# smartwatch_class_2_justincase.net
KiCad netlist of a schematic drawn in EAGLE
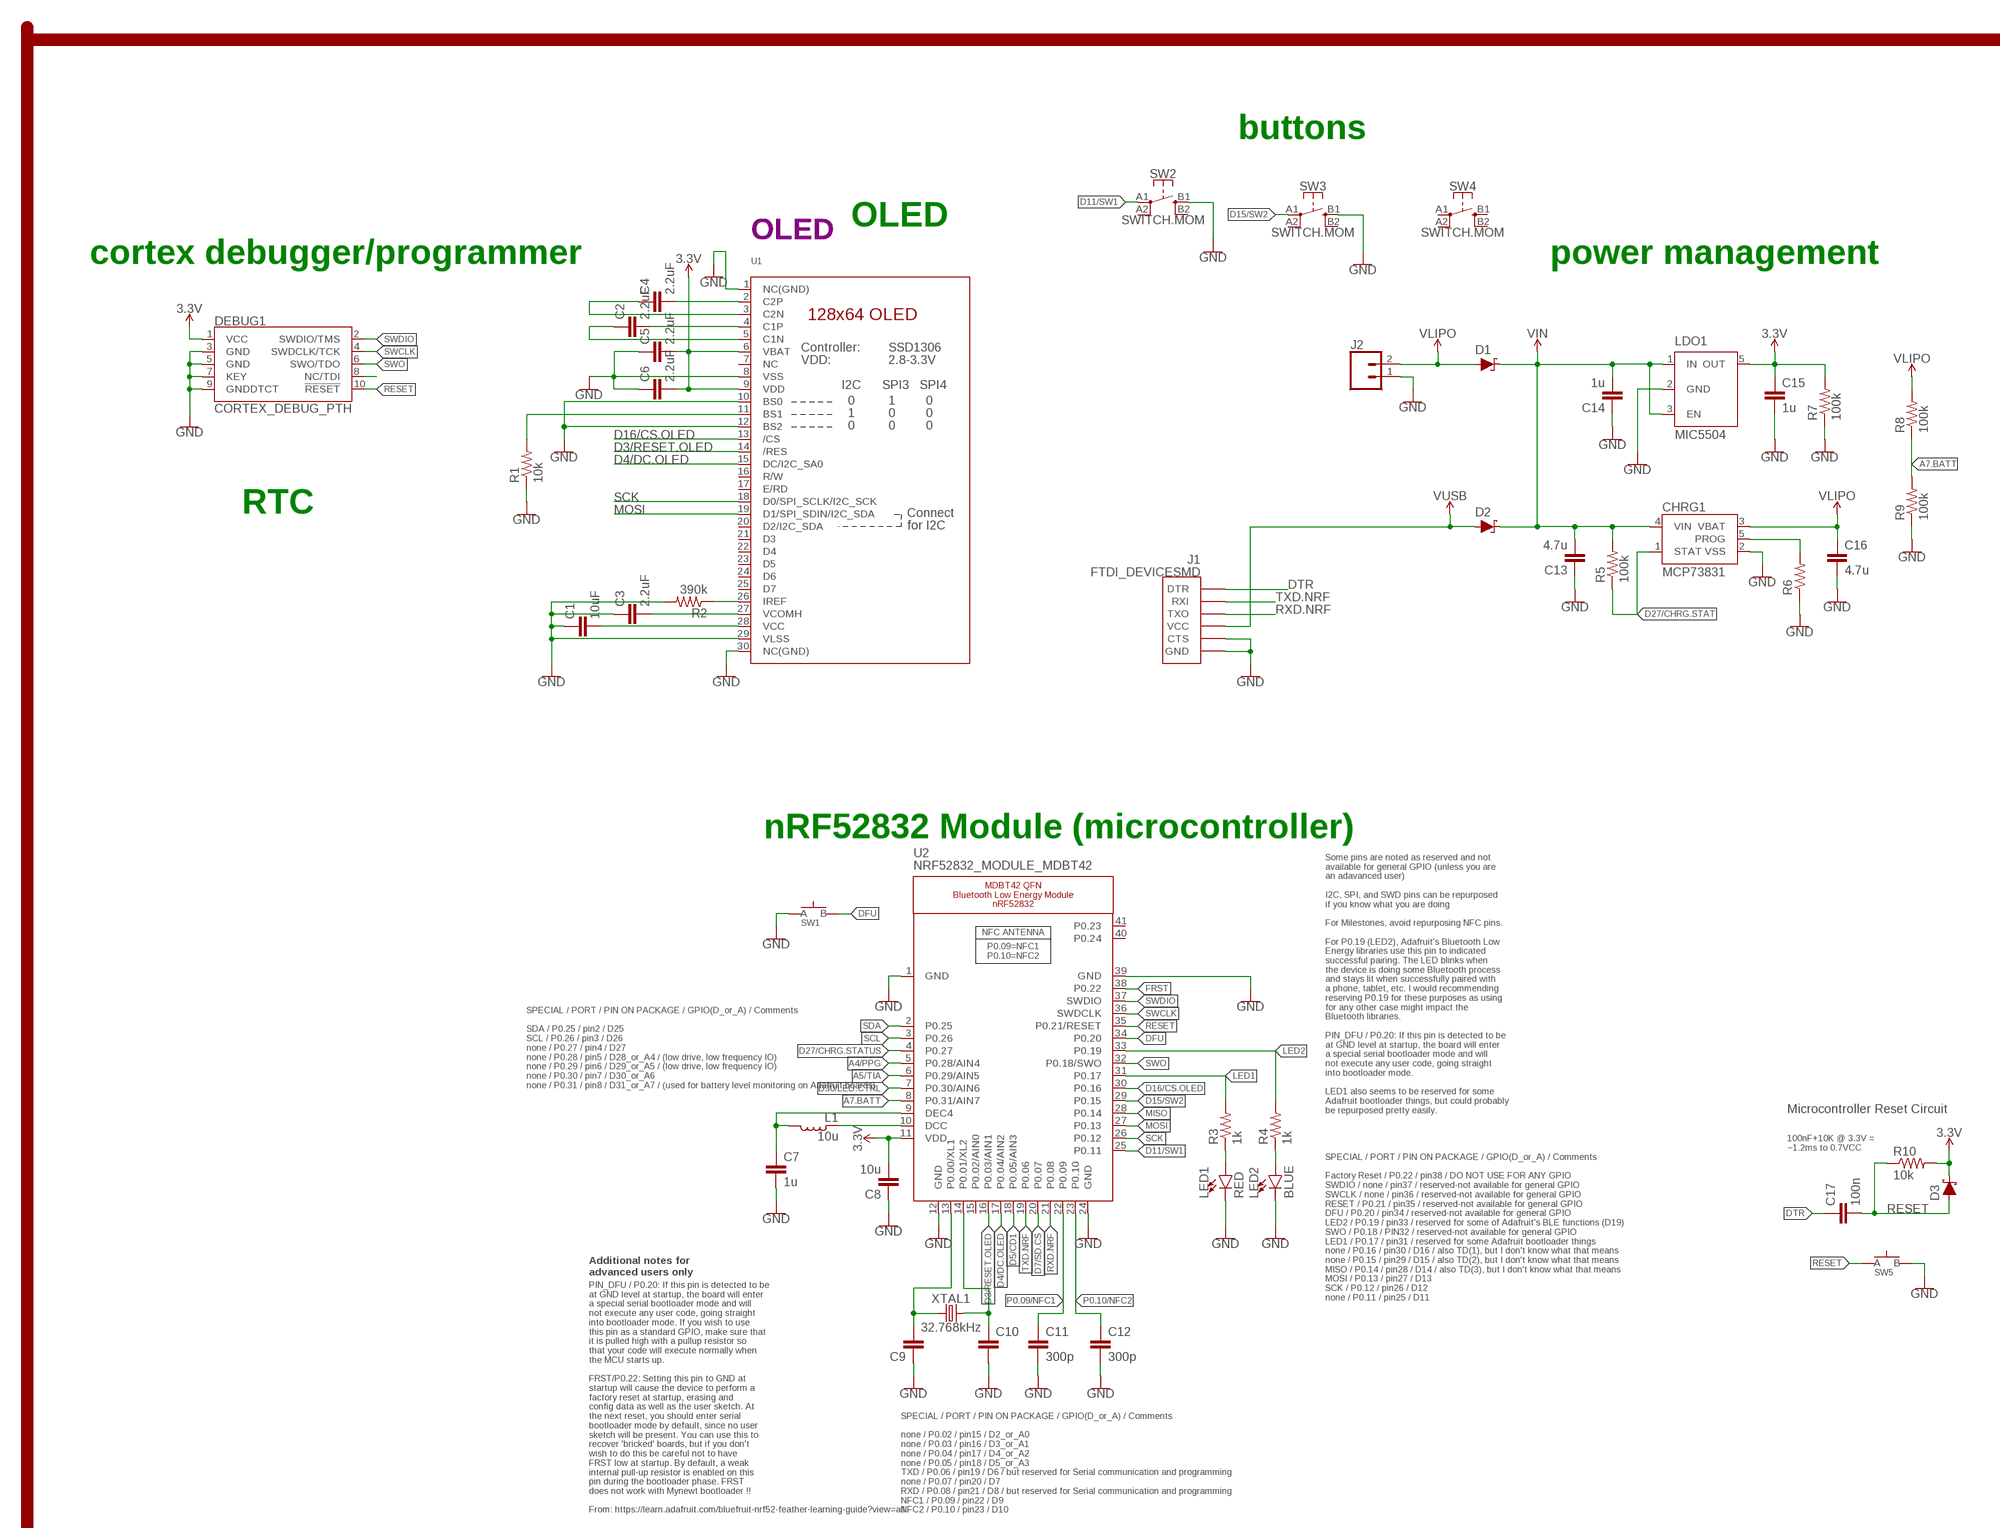
[diagram p0: schematic, sheet 1, part 1 of 2]
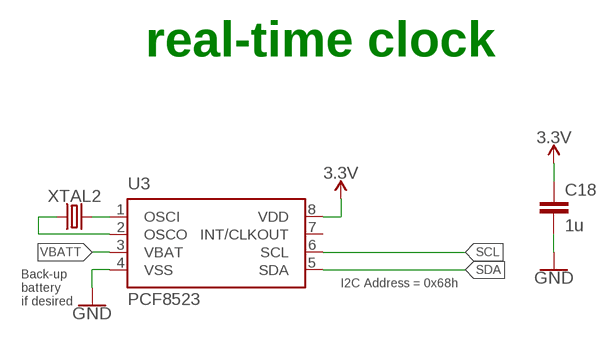
[diagram p1: schematic, sheet 1, part 2 of 2]

(export (version "E")
  (design (tool "Eeschema 10.0.6"))
  (components
    (comp (ref "C1")
      (value "10uF")
      (footprint "eagle-import:C0603")
      (libsource (lib "eagle-import") (part "CAPACITOR0603"))
    )
    (comp (ref "C2")
      (value "2.2uF")
      (footprint "eagle-import:C0603")
      (libsource (lib "eagle-import") (part "CAPACITOR0603"))
    )
    (comp (ref "C3")
      (value "2.2uF")
      (footprint "eagle-import:C0603")
      (libsource (lib "eagle-import") (part "CAPACITOR0603"))
    )
    (comp (ref "C4")
      (value "2.2uF")
      (footprint "eagle-import:C0603")
      (libsource (lib "eagle-import") (part "CAPACITOR0603"))
    )
    (comp (ref "C5")
      (value "2.2uF")
      (footprint "eagle-import:C0603")
      (libsource (lib "eagle-import") (part "CAPACITOR0603"))
    )
    (comp (ref "C6")
      (value "2.2uF")
      (footprint "eagle-import:C0603")
      (libsource (lib "eagle-import") (part "CAPACITOR0603"))
    )
    (comp (ref "C7")
      (value "1u")
      (footprint "eagle-import:C0603")
      (libsource (lib "eagle-import") (part "CAPACITOR0603"))
    )
    (comp (ref "C8")
      (value "10u")
      (footprint "eagle-import:C0805")
      (libsource (lib "eagle-import") (part "CAPACITOR0805"))
    )
    (comp (ref "C9")
      (value "CAPACITOR0603")
      (footprint "eagle-import:C0603")
      (libsource (lib "eagle-import") (part "CAPACITOR0603"))
    )
    (comp (ref "C10")
      (value "CAPACITOR0603")
      (footprint "eagle-import:C0603")
      (libsource (lib "eagle-import") (part "CAPACITOR0603"))
    )
    (comp (ref "C11")
      (value "300p")
      (footprint "eagle-import:C0603")
      (libsource (lib "eagle-import") (part "CAPACITOR0603"))
    )
    (comp (ref "C12")
      (value "300p")
      (footprint "eagle-import:C0603")
      (libsource (lib "eagle-import") (part "CAPACITOR0603"))
    )
    (comp (ref "C13")
      (value "4.7u")
      (footprint "eagle-import:C0603")
      (libsource (lib "eagle-import") (part "CAPACITOR0603"))
    )
    (comp (ref "C14")
      (value "1u")
      (footprint "eagle-import:C0603")
      (libsource (lib "eagle-import") (part "CAPACITOR0603"))
    )
    (comp (ref "C15")
      (value "1u")
      (footprint "eagle-import:C0603")
      (libsource (lib "eagle-import") (part "CAPACITOR0603"))
    )
    (comp (ref "C16")
      (value "4.7u")
      (footprint "eagle-import:C0603")
      (libsource (lib "eagle-import") (part "CAPACITOR0603"))
    )
    (comp (ref "C17")
      (value "100n")
      (footprint "eagle-import:C0603")
      (libsource (lib "eagle-import") (part "CAPACITOR0603"))
    )
    (comp (ref "C18")
      (value "1u")
      (footprint "eagle-import:C0603")
      (libsource (lib "eagle-import") (part "CAPACITOR0603"))
    )
    (comp (ref "CHRG1")
      (value "MCP73831")
      (footprint "eagle-import:SOT23-5")
      (libsource (lib "eagle-import") (part "MCP73831"))
    )
    (comp (ref "D1")
      (value "SCHOTTKY-USC")
      (footprint "eagle-import:USC")
      (libsource (lib "eagle-import") (part "SCHOTTKY-USC"))
    )
    (comp (ref "D2")
      (value "SCHOTTKY-USC")
      (footprint "eagle-import:USC")
      (libsource (lib "eagle-import") (part "SCHOTTKY-USC"))
    )
    (comp (ref "D3")
      (value "SCHOTTKY-USC")
      (footprint "eagle-import:USC")
      (libsource (lib "eagle-import") (part "SCHOTTKY-USC"))
    )
    (comp (ref "DEBUG1")
      (value "CORTEX_DEBUG_PTH")
      (footprint "eagle-import:2X5-PTH-1.27MM")
      (libsource (lib "eagle-import") (part "CORTEX_DEBUG_PTH"))
    )
    (comp (ref "J1")
      (value "FTDI_DEVICESMD")
      (footprint "eagle-import:FTDI-SMD")
      (libsource (lib "eagle-import") (part "FTDI_DEVICESMD"))
    )
    (comp (ref "J2")
      (value "CONN_02")
      (footprint "eagle-import:1X02")
      (libsource (lib "eagle-import") (part "CONN_02"))
    )
    (comp (ref "L1")
      (value "10u")
      (footprint "eagle-import:L0603")
      (libsource (lib "eagle-import") (part "INDUCTOR0603"))
    )
    (comp (ref "LDO1")
      (value "MIC5504")
      (footprint "eagle-import:SOT23-5")
      (libsource (lib "eagle-import") (part "MIC5504"))
    )
    (comp (ref "LED1")
      (value "RED")
      (footprint "eagle-import:LED-0603")
      (libsource (lib "eagle-import") (part "LED0603"))
    )
    (comp (ref "LED2")
      (value "BLUE")
      (footprint "eagle-import:LED-0603")
      (libsource (lib "eagle-import") (part "LED0603"))
    )
    (comp (ref "R1")
      (value "10k")
      (footprint "eagle-import:R0603")
      (libsource (lib "eagle-import") (part "RESISTOR0603"))
    )
    (comp (ref "R2")
      (value "390k")
      (footprint "eagle-import:R0603")
      (libsource (lib "eagle-import") (part "RESISTOR0603"))
    )
    (comp (ref "R3")
      (value "1k")
      (footprint "eagle-import:R0603")
      (libsource (lib "eagle-import") (part "RESISTOR0603"))
    )
    (comp (ref "R4")
      (value "1k")
      (footprint "eagle-import:R0603")
      (libsource (lib "eagle-import") (part "RESISTOR0603"))
    )
    (comp (ref "R5")
      (value "100k")
      (footprint "eagle-import:R0603")
      (libsource (lib "eagle-import") (part "RESISTOR0603"))
    )
    (comp (ref "R6")
      (value "RESISTOR0603")
      (footprint "eagle-import:R0603")
      (libsource (lib "eagle-import") (part "RESISTOR0603"))
    )
    (comp (ref "R7")
      (value "100k")
      (footprint "eagle-import:R0603")
      (libsource (lib "eagle-import") (part "RESISTOR0603"))
    )
    (comp (ref "R8")
      (value "100k")
      (footprint "eagle-import:R0603")
      (libsource (lib "eagle-import") (part "RESISTOR0603"))
    )
    (comp (ref "R9")
      (value "100k")
      (footprint "eagle-import:R0603")
      (libsource (lib "eagle-import") (part "RESISTOR0603"))
    )
    (comp (ref "R10")
      (value "10k")
      (footprint "eagle-import:R0603")
      (libsource (lib "eagle-import") (part "RESISTOR0603"))
    )
    (comp (ref "SW1")
      (value "SPST-PTS830GG140-COPY.1-3")
      (footprint "eagle-import:BUTTON-GULLWING")
      (libsource (lib "eagle-import") (part "SPST-PTS830GG140-COPY.1-3"))
    )
    (comp (ref "SW2")
      (value "SWITCH.MOM")
      (footprint "eagle-import:TACTILE_SWITCH_SMD_6.2MM_TALL")
      (libsource (lib "eagle-import") (part "SWITCH.MOM"))
    )
    (comp (ref "SW3")
      (value "SWITCH.MOM")
      (footprint "eagle-import:TACTILE_SWITCH_SMD_6.2MM_TALL")
      (libsource (lib "eagle-import") (part "SWITCH.MOM"))
    )
    (comp (ref "SW4")
      (value "SWITCH.MOM")
      (footprint "eagle-import:TACTILE_SWITCH_SMD_6.2MM_TALL")
      (libsource (lib "eagle-import") (part "SWITCH.MOM"))
    )
    (comp (ref "SW5")
      (value "SPST-PTS830GG140-COPY.1-3")
      (footprint "eagle-import:BUTTON-GULLWING")
      (libsource (lib "eagle-import") (part "SPST-PTS830GG140-COPY.1-3"))
    )
    (comp (ref "U1")
      (value "DISP_OLED_UG-2864HSWEG01-NO-WRAPAROUND")
      (footprint "eagle-import:UG-2864HSWEG01_0.96IN_NO-WRAPAROUND")
      (libsource (lib "eagle-import") (part "DISP_OLED_UG-2864HSWEG01-NO-WRAPAROUND"))
    )
    (comp (ref "U2")
      (value "NRF52832_MODULE_MDBT42")
      (footprint "eagle-import:BLE_MODULE_RAYTAC_MDBT42")
      (libsource (lib "eagle-import") (part "NRF52832_MODULE_MDBT42"))
    )
    (comp (ref "U3")
      (value "PCF8523")
      (footprint "eagle-import:SO8")
      (libsource (lib "eagle-import") (part "PCF8523"))
    )
    (comp (ref "XTAL1")
      (value "32.768kHz")
      (footprint "eagle-import:2-SMD.NOLEAD.2.0MMTO1.2MM")
      (libsource (lib "eagle-import") (part "CRYSTALECS-.327-12.5-12-C-TR"))
    )
    (comp (ref "XTAL2")
      (value "32.7680kHz")
      (footprint "eagle-import:2-SMD.NOLEAD.2.0MMTO1.2MM")
      (fields (field (name "FREQ") "32.7680KHZ"))
      (libsource (lib "eagle-import") (part "CRYSTALECS-.327-12.5-12-C-TR"))
    )
  )
  (nets
    (net (code "1") (name "3.3V") (class "Default")
      (node (ref "C15") (pin "1") (pinfunction "1_1") (pintype "passive"))
      (node (ref "C18") (pin "1") (pinfunction "1_1") (pintype "passive"))
      (node (ref "C5") (pin "2") (pinfunction "2_2") (pintype "passive"))
      (node (ref "C6") (pin "2") (pinfunction "2_2") (pintype "passive"))
      (node (ref "C8") (pin "2") (pinfunction "2_2") (pintype "passive"))
      (node (ref "D3") (pin "-") (pinfunction "C_-") (pintype "passive"))
      (node (ref "DEBUG1") (pin "1") (pinfunction "VCC_1") (pintype "bidirectional"))
      (node (ref "LDO1") (pin "5") (pinfunction "OUT_5") (pintype "bidirectional"))
      (node (ref "R10") (pin "2") (pinfunction "2_2") (pintype "passive"))
      (node (ref "R7") (pin "2") (pinfunction "2_2") (pintype "passive"))
      (node (ref "U1") (pin "6") (pinfunction "VBAT_6") (pintype "input"))
      (node (ref "U1") (pin "9") (pinfunction "VDD_9") (pintype "power_in"))
      (node (ref "U2") (pin "11") (pinfunction "VDD_11") (pintype "bidirectional"))
      (node (ref "U3") (pin "8") (pinfunction "VDD_8") (pintype "power_in"))
    )
    (net (code "2") (name "A4{slash}PPG") (class "Default")
      (node (ref "U2") (pin "5") (pinfunction "P0.28/AIN4_5") (pintype "bidirectional"))
    )
    (net (code "3") (name "A5{slash}TIA") (class "Default")
      (node (ref "U2") (pin "6") (pinfunction "P0.29/AIN5_6") (pintype "bidirectional"))
    )
    (net (code "4") (name "A7.BATT") (class "Default")
      (node (ref "R8") (pin "1") (pinfunction "1_1") (pintype "passive"))
      (node (ref "R9") (pin "2") (pinfunction "2_2") (pintype "passive"))
      (node (ref "U2") (pin "8") (pinfunction "P0.31/AIN7_8") (pintype "bidirectional"))
    )
    (net (code "5") (name "D3{slash}RESET.OLED") (class "Default")
      (node (ref "U1") (pin "14") (pinfunction "/RES_14") (pintype "input"))
      (node (ref "U2") (pin "16") (pinfunction "P0.03/AIN1_16") (pintype "bidirectional"))
    )
    (net (code "6") (name "D4{slash}DC.OLED") (class "Default")
      (node (ref "U1") (pin "15") (pinfunction "DC/I2C_SA0_15") (pintype "input"))
      (node (ref "U2") (pin "17") (pinfunction "P0.04/AIN2_17") (pintype "bidirectional"))
    )
    (net (code "7") (name "D5{slash}CD1") (class "Default")
      (node (ref "U2") (pin "18") (pinfunction "P0.05/AIN3_18") (pintype "bidirectional"))
    )
    (net (code "8") (name "D7{slash}SD.CS") (class "Default")
      (node (ref "U2") (pin "20") (pinfunction "P0.07_20") (pintype "bidirectional"))
    )
    (net (code "9") (name "D11{slash}SW1") (class "Default")
      (node (ref "SW2") (pin "A1") (pinfunction "1_A1") (pintype "passive"))
      (node (ref "U2") (pin "25") (pinfunction "P0.11_25") (pintype "bidirectional"))
    )
    (net (code "10") (name "D15{slash}SW2") (class "Default")
      (node (ref "SW3") (pin "A1") (pinfunction "1_A1") (pintype "passive"))
      (node (ref "U2") (pin "29") (pinfunction "P0.15_29") (pintype "bidirectional"))
    )
    (net (code "11") (name "D16{slash}CS.OLED") (class "Default")
      (node (ref "U1") (pin "13") (pinfunction "/CS_13") (pintype "input"))
      (node (ref "U2") (pin "30") (pinfunction "P0.16_30") (pintype "bidirectional"))
    )
    (net (code "12") (name "D27{slash}CHRG.STAT") (class "Default")
      (node (ref "CHRG1") (pin "1") (pinfunction "STAT_1") (pintype "output"))
      (node (ref "R5") (pin "1") (pinfunction "1_1") (pintype "passive"))
    )
    (net (code "13") (name "D27{slash}CHRG.STATUS") (class "Default")
      (node (ref "U2") (pin "4") (pinfunction "P0.27_4") (pintype "bidirectional"))
    )
    (net (code "14") (name "D30{slash}LED.CTRL") (class "Default")
      (node (ref "U2") (pin "7") (pinfunction "P0.30/AIN6_7") (pintype "bidirectional"))
    )
    (net (code "15") (name "DFU") (class "Default")
      (node (ref "SW1") (pin "3") (pinfunction "B_3") (pintype "bidirectional"))
      (node (ref "U2") (pin "34") (pinfunction "P0.20_34") (pintype "bidirectional"))
    )
    (net (code "16") (name "DTR") (class "Default")
      (node (ref "C17") (pin "1") (pinfunction "1_1") (pintype "passive"))
      (node (ref "J1") (pin "DTR") (pinfunction "DTR_DTR") (pintype "bidirectional"))
    )
    (net (code "17") (name "FRST") (class "Default")
      (node (ref "U2") (pin "38") (pinfunction "P0.22_38") (pintype "bidirectional"))
    )
    (net (code "18") (name "GND") (class "Default")
      (node (ref "C1") (pin "1") (pinfunction "1_1") (pintype "passive"))
      (node (ref "C10") (pin "2") (pinfunction "2_2") (pintype "passive"))
      (node (ref "C11") (pin "2") (pinfunction "2_2") (pintype "passive"))
      (node (ref "C12") (pin "2") (pinfunction "2_2") (pintype "passive"))
      (node (ref "C13") (pin "1") (pinfunction "1_1") (pintype "passive"))
      (node (ref "C14") (pin "1") (pinfunction "1_1") (pintype "passive"))
      (node (ref "C15") (pin "2") (pinfunction "2_2") (pintype "passive"))
      (node (ref "C16") (pin "2") (pinfunction "2_2") (pintype "passive"))
      (node (ref "C18") (pin "2") (pinfunction "2_2") (pintype "passive"))
      (node (ref "C3") (pin "1") (pinfunction "1_1") (pintype "passive"))
      (node (ref "C5") (pin "1") (pinfunction "1_1") (pintype "passive"))
      (node (ref "C6") (pin "1") (pinfunction "1_1") (pintype "passive"))
      (node (ref "C7") (pin "2") (pinfunction "2_2") (pintype "passive"))
      (node (ref "C8") (pin "1") (pinfunction "1_1") (pintype "passive"))
      (node (ref "C9") (pin "1") (pinfunction "1_1") (pintype "passive"))
      (node (ref "CHRG1") (pin "2") (pinfunction "VSS_2") (pintype "power_in"))
      (node (ref "DEBUG1") (pin "3") (pinfunction "GND_3") (pintype "bidirectional"))
      (node (ref "DEBUG1") (pin "5") (pinfunction "GND_5") (pintype "bidirectional"))
      (node (ref "DEBUG1") (pin "7") (pinfunction "KEY_7") (pintype "bidirectional"))
      (node (ref "DEBUG1") (pin "9") (pinfunction "GNDDTCT_9") (pintype "bidirectional"))
      (node (ref "J1") (pin "CTS") (pinfunction "CTS_CTS") (pintype "bidirectional"))
      (node (ref "J1") (pin "GND") (pinfunction "GND_GND") (pintype "bidirectional"))
      (node (ref "J2") (pin "1") (pinfunction "1_1") (pintype "passive"))
      (node (ref "LDO1") (pin "2") (pinfunction "GND_2") (pintype "bidirectional"))
      (node (ref "LED1") (pin "C") (pinfunction "C_C") (pintype "passive"))
      (node (ref "LED2") (pin "C") (pinfunction "C_C") (pintype "passive"))
      (node (ref "R1") (pin "1") (pinfunction "1_1") (pintype "passive"))
      (node (ref "R2") (pin "2") (pinfunction "2_2") (pintype "passive"))
      (node (ref "R6") (pin "1") (pinfunction "1_1") (pintype "passive"))
      (node (ref "R7") (pin "1") (pinfunction "1_1") (pintype "passive"))
      (node (ref "R9") (pin "1") (pinfunction "1_1") (pintype "passive"))
      (node (ref "SW1") (pin "1") (pinfunction "A_1") (pintype "bidirectional"))
      (node (ref "SW2") (pin "B1") (pinfunction "3_B1") (pintype "passive"))
      (node (ref "SW3") (pin "B1") (pinfunction "3_B1") (pintype "passive"))
      (node (ref "SW5") (pin "3") (pinfunction "B_3") (pintype "bidirectional"))
      (node (ref "U1") (pin "1") (pinfunction "NC(GND)_1") (pintype "input"))
      (node (ref "U1") (pin "10") (pinfunction "BS0_10") (pintype "input"))
      (node (ref "U1") (pin "12") (pinfunction "BS2_12") (pintype "input"))
      (node (ref "U1") (pin "29") (pinfunction "VLSS_29") (pintype "power_in"))
      (node (ref "U1") (pin "30") (pinfunction "NC(GND)_30") (pintype "input"))
      (node (ref "U1") (pin "8") (pinfunction "VSS_8") (pintype "power_in"))
      (node (ref "U2") (pin "1") (pinfunction "GND_1") (pintype "bidirectional"))
      (node (ref "U2") (pin "12") (pinfunction "GND_12") (pintype "bidirectional"))
      (node (ref "U2") (pin "24") (pinfunction "GND_24") (pintype "bidirectional"))
      (node (ref "U2") (pin "39") (pinfunction "GND_39") (pintype "bidirectional"))
      (node (ref "U3") (pin "4") (pinfunction "VSS_4") (pintype "power_in"))
    )
    (net (code "19") (name "LED1") (class "Default")
      (node (ref "R3") (pin "2") (pinfunction "2_2") (pintype "passive"))
      (node (ref "U2") (pin "31") (pinfunction "P0.17_31") (pintype "bidirectional"))
    )
    (net (code "20") (name "LED2") (class "Default")
      (node (ref "R4") (pin "2") (pinfunction "2_2") (pintype "passive"))
      (node (ref "U2") (pin "33") (pinfunction "P0.19_33") (pintype "bidirectional"))
    )
    (net (code "21") (name "MISO") (class "Default")
      (node (ref "U2") (pin "28") (pinfunction "P0.14_28") (pintype "bidirectional"))
    )
    (net (code "22") (name "MOSI") (class "Default")
      (node (ref "U1") (pin "19") (pinfunction "D1/SPI_SDIN/I2C_SDA_19") (pintype "bidirectional"))
      (node (ref "U2") (pin "27") (pinfunction "P0.13_27") (pintype "bidirectional"))
    )
    (net (code "23") (name "Net-(CHRG1-PROG)") (class "Default")
      (node (ref "CHRG1") (pin "5") (pinfunction "PROG_5") (pintype "input"))
      (node (ref "R6") (pin "2") (pinfunction "2_2") (pintype "passive"))
    )
    (net (code "24") (name "Net-(LED1-PadA)") (class "Default")
      (node (ref "LED1") (pin "A") (pinfunction "A_A") (pintype "passive"))
      (node (ref "R3") (pin "1") (pinfunction "1_1") (pintype "passive"))
    )
    (net (code "25") (name "Net-(LED2-PadA)") (class "Default")
      (node (ref "LED2") (pin "A") (pinfunction "A_A") (pintype "passive"))
      (node (ref "R4") (pin "1") (pinfunction "1_1") (pintype "passive"))
    )
    (net (code "26") (name "Net-(U1-BS1)") (class "Default")
      (node (ref "R1") (pin "2") (pinfunction "2_2") (pintype "passive"))
      (node (ref "U1") (pin "11") (pinfunction "BS1_11") (pintype "input"))
    )
    (net (code "27") (name "Net-(U1-C1N)") (class "Default")
      (node (ref "C2") (pin "1") (pinfunction "1_1") (pintype "passive"))
      (node (ref "U1") (pin "5") (pinfunction "C1N_5") (pintype "input"))
    )
    (net (code "28") (name "Net-(U1-C1P)") (class "Default")
      (node (ref "C2") (pin "2") (pinfunction "2_2") (pintype "passive"))
      (node (ref "U1") (pin "4") (pinfunction "C1P_4") (pintype "input"))
    )
    (net (code "29") (name "Net-(U1-C2N)") (class "Default")
      (node (ref "C4") (pin "1") (pinfunction "1_1") (pintype "passive"))
      (node (ref "U1") (pin "3") (pinfunction "C2N_3") (pintype "input"))
    )
    (net (code "30") (name "Net-(U1-C2P)") (class "Default")
      (node (ref "C4") (pin "2") (pinfunction "2_2") (pintype "passive"))
      (node (ref "U1") (pin "2") (pinfunction "C2P_2") (pintype "input"))
    )
    (net (code "31") (name "Net-(U1-IREF)") (class "Default")
      (node (ref "R2") (pin "1") (pinfunction "1_1") (pintype "passive"))
      (node (ref "U1") (pin "26") (pinfunction "IREF_26") (pintype "input"))
    )
    (net (code "32") (name "Net-(U1-VCC)") (class "Default")
      (node (ref "C1") (pin "2") (pinfunction "2_2") (pintype "passive"))
      (node (ref "U1") (pin "28") (pinfunction "VCC_28") (pintype "power_in"))
    )
    (net (code "33") (name "Net-(U1-VCOMH)") (class "Default")
      (node (ref "C3") (pin "2") (pinfunction "2_2") (pintype "passive"))
      (node (ref "U1") (pin "27") (pinfunction "VCOMH_27") (pintype "output"))
    )
    (net (code "34") (name "Net-(U2-DCC)") (class "Default")
      (node (ref "L1") (pin "1") (pinfunction "1_1") (pintype "passive"))
      (node (ref "U2") (pin "10") (pinfunction "DCC_10") (pintype "bidirectional"))
    )
    (net (code "35") (name "Net-(U2-DEC4)") (class "Default")
      (node (ref "C7") (pin "1") (pinfunction "1_1") (pintype "passive"))
      (node (ref "L1") (pin "2") (pinfunction "2_2") (pintype "passive"))
      (node (ref "U2") (pin "9") (pinfunction "DEC4_9") (pintype "bidirectional"))
    )
    (net (code "36") (name "Net-(U2-P0.00{slash}XL1)") (class "Default")
      (node (ref "C9") (pin "2") (pinfunction "2_2") (pintype "passive"))
      (node (ref "U2") (pin "13") (pinfunction "P0.00/XL1_13") (pintype "bidirectional"))
      (node (ref "XTAL1") (pin "P$1") (pinfunction "1_P$1") (pintype "passive"))
    )
    (net (code "37") (name "Net-(U2-P0.01{slash}XL2)") (class "Default")
      (node (ref "C10") (pin "1") (pinfunction "1_1") (pintype "passive"))
      (node (ref "U2") (pin "14") (pinfunction "P0.01/XL2_14") (pintype "bidirectional"))
      (node (ref "XTAL1") (pin "P$2") (pinfunction "2_P$2") (pintype "passive"))
    )
    (net (code "38") (name "Net-(U3-OSCI)") (class "Default")
      (node (ref "U3") (pin "1") (pinfunction "OSCI_1") (pintype "bidirectional"))
      (node (ref "XTAL2") (pin "P$2") (pinfunction "2_P$2") (pintype "passive"))
    )
    (net (code "39") (name "Net-(U3-OSCO)") (class "Default")
      (node (ref "U3") (pin "2") (pinfunction "OSCO_2") (pintype "bidirectional"))
      (node (ref "XTAL2") (pin "P$1") (pinfunction "1_P$1") (pintype "passive"))
    )
    (net (code "40") (name "P0.09{slash}NFC1") (class "Default")
      (node (ref "C11") (pin "1") (pinfunction "1_1") (pintype "passive"))
      (node (ref "U2") (pin "22") (pinfunction "P0.09_22") (pintype "bidirectional"))
    )
    (net (code "41") (name "P0.10{slash}NFC2") (class "Default")
      (node (ref "C12") (pin "1") (pinfunction "1_1") (pintype "passive"))
      (node (ref "U2") (pin "23") (pinfunction "P0.10_23") (pintype "bidirectional"))
    )
    (net (code "42") (name "RESET") (class "Default")
      (node (ref "C17") (pin "2") (pinfunction "2_2") (pintype "passive"))
      (node (ref "D3") (pin "+") (pinfunction "A_+") (pintype "passive"))
      (node (ref "DEBUG1") (pin "10") (pinfunction "~{RESET}_10") (pintype "bidirectional"))
      (node (ref "R10") (pin "1") (pinfunction "1_1") (pintype "passive"))
      (node (ref "SW5") (pin "1") (pinfunction "A_1") (pintype "bidirectional"))
      (node (ref "U2") (pin "35") (pinfunction "P0.21/RESET_35") (pintype "bidirectional"))
    )
    (net (code "43") (name "RXD.NRF") (class "Default")
      (node (ref "J1") (pin "TXO") (pinfunction "TXO_TXO") (pintype "bidirectional"))
      (node (ref "U2") (pin "21") (pinfunction "P0.08_21") (pintype "bidirectional"))
    )
    (net (code "44") (name "SCK") (class "Default")
      (node (ref "U1") (pin "18") (pinfunction "D0/SPI_SCLK/I2C_SCK_18") (pintype "bidirectional"))
      (node (ref "U2") (pin "26") (pinfunction "P0.12_26") (pintype "bidirectional"))
    )
    (net (code "45") (name "SCL") (class "Default")
      (node (ref "U2") (pin "3") (pinfunction "P0.26_3") (pintype "bidirectional"))
      (node (ref "U3") (pin "6") (pinfunction "SCL_6") (pintype "bidirectional"))
    )
    (net (code "46") (name "SDA") (class "Default")
      (node (ref "U2") (pin "2") (pinfunction "P0.25_2") (pintype "bidirectional"))
      (node (ref "U3") (pin "5") (pinfunction "SDA_5") (pintype "bidirectional"))
    )
    (net (code "47") (name "SWCLK") (class "Default")
      (node (ref "DEBUG1") (pin "4") (pinfunction "SWDCLK/TCK_4") (pintype "bidirectional"))
      (node (ref "U2") (pin "36") (pinfunction "SWDCLK_36") (pintype "bidirectional"))
    )
    (net (code "48") (name "SWDIO") (class "Default")
      (node (ref "DEBUG1") (pin "2") (pinfunction "SWDIO/TMS_2") (pintype "bidirectional"))
      (node (ref "U2") (pin "37") (pinfunction "SWDIO_37") (pintype "bidirectional"))
    )
    (net (code "49") (name "SWO") (class "Default")
      (node (ref "DEBUG1") (pin "6") (pinfunction "SWO/TDO_6") (pintype "bidirectional"))
      (node (ref "U2") (pin "32") (pinfunction "P0.18/SWO_32") (pintype "bidirectional"))
    )
    (net (code "50") (name "TXD.NRF") (class "Default")
      (node (ref "J1") (pin "RXI") (pinfunction "RXI_RXI") (pintype "bidirectional"))
      (node (ref "U2") (pin "19") (pinfunction "P0.06_19") (pintype "bidirectional"))
    )
    (net (code "51") (name "VBATT") (class "Default")
      (node (ref "U3") (pin "3") (pinfunction "VBAT_3") (pintype "power_in"))
    )
    (net (code "52") (name "VIN") (class "Default")
      (node (ref "C13") (pin "2") (pinfunction "2_2") (pintype "passive"))
      (node (ref "C14") (pin "2") (pinfunction "2_2") (pintype "passive"))
      (node (ref "CHRG1") (pin "4") (pinfunction "VIN_4") (pintype "power_in"))
      (node (ref "D1") (pin "-") (pinfunction "C_-") (pintype "passive"))
      (node (ref "D2") (pin "-") (pinfunction "C_-") (pintype "passive"))
      (node (ref "LDO1") (pin "1") (pinfunction "IN_1") (pintype "bidirectional"))
      (node (ref "LDO1") (pin "3") (pinfunction "EN_3") (pintype "bidirectional"))
      (node (ref "R5") (pin "2") (pinfunction "2_2") (pintype "passive"))
    )
    (net (code "53") (name "VLIPO") (class "Default")
      (node (ref "C16") (pin "1") (pinfunction "1_1") (pintype "passive"))
      (node (ref "CHRG1") (pin "3") (pinfunction "VBAT_3") (pintype "power_in"))
      (node (ref "D1") (pin "+") (pinfunction "A_+") (pintype "passive"))
      (node (ref "J2") (pin "2") (pinfunction "2_2") (pintype "passive"))
      (node (ref "R8") (pin "2") (pinfunction "2_2") (pintype "passive"))
    )
    (net (code "54") (name "VUSB") (class "Default")
      (node (ref "D2") (pin "+") (pinfunction "A_+") (pintype "passive"))
      (node (ref "J1") (pin "VCC") (pinfunction "VCC_VCC") (pintype "bidirectional"))
    )
    (net (code "55") (name "unconnected-(DEBUG1-NC{slash}TDI-Pad8)") (class "Default")
      (node (ref "DEBUG1") (pin "8") (pinfunction "NC/TDI_8") (pintype "bidirectional"))
    )
    (net (code "56") (name "unconnected-(SW2-2-PadA2)") (class "Default")
      (node (ref "SW2") (pin "A2") (pinfunction "2_A2") (pintype "passive"))
    )
    (net (code "57") (name "unconnected-(SW2-4-PadB2)") (class "Default")
      (node (ref "SW2") (pin "B2") (pinfunction "4_B2") (pintype "passive"))
    )
    (net (code "58") (name "unconnected-(SW3-2-PadA2)") (class "Default")
      (node (ref "SW3") (pin "A2") (pinfunction "2_A2") (pintype "passive"))
    )
    (net (code "59") (name "unconnected-(SW3-4-PadB2)") (class "Default")
      (node (ref "SW3") (pin "B2") (pinfunction "4_B2") (pintype "passive"))
    )
    (net (code "60") (name "unconnected-(SW4-1-PadA1)") (class "Default")
      (node (ref "SW4") (pin "A1") (pinfunction "1_A1") (pintype "passive"))
    )
    (net (code "61") (name "unconnected-(SW4-2-PadA2)") (class "Default")
      (node (ref "SW4") (pin "A2") (pinfunction "2_A2") (pintype "passive"))
    )
    (net (code "62") (name "unconnected-(SW4-3-PadB1)") (class "Default")
      (node (ref "SW4") (pin "B1") (pinfunction "3_B1") (pintype "passive"))
    )
    (net (code "63") (name "unconnected-(SW4-4-PadB2)") (class "Default")
      (node (ref "SW4") (pin "B2") (pinfunction "4_B2") (pintype "passive"))
    )
    (net (code "64") (name "unconnected-(U1-D2{slash}I2C_SDA-Pad20)") (class "Default")
      (node (ref "U1") (pin "20") (pinfunction "D2/I2C_SDA_20") (pintype "bidirectional"))
    )
    (net (code "65") (name "unconnected-(U1-D3-Pad21)") (class "Default")
      (node (ref "U1") (pin "21") (pinfunction "D3_21") (pintype "bidirectional"))
    )
    (net (code "66") (name "unconnected-(U1-D4-Pad22)") (class "Default")
      (node (ref "U1") (pin "22") (pinfunction "D4_22") (pintype "bidirectional"))
    )
    (net (code "67") (name "unconnected-(U1-D5-Pad23)") (class "Default")
      (node (ref "U1") (pin "23") (pinfunction "D5_23") (pintype "bidirectional"))
    )
    (net (code "68") (name "unconnected-(U1-D6-Pad24)") (class "Default")
      (node (ref "U1") (pin "24") (pinfunction "D6_24") (pintype "bidirectional"))
    )
    (net (code "69") (name "unconnected-(U1-D7-Pad25)") (class "Default")
      (node (ref "U1") (pin "25") (pinfunction "D7_25") (pintype "bidirectional"))
    )
    (net (code "70") (name "unconnected-(U1-E{slash}RD-Pad17)") (class "Default")
      (node (ref "U1") (pin "17") (pinfunction "E/RD_17") (pintype "input"))
    )
    (net (code "71") (name "unconnected-(U1-NC-Pad7)") (class "Default")
      (node (ref "U1") (pin "7") (pinfunction "NC_7") (pintype "no_connect"))
    )
    (net (code "72") (name "unconnected-(U1-R{slash}W-Pad16)") (class "Default")
      (node (ref "U1") (pin "16") (pinfunction "R/W_16") (pintype "input"))
    )
    (net (code "73") (name "unconnected-(U2-P0.02{slash}AIN0-Pad15)") (class "Default")
      (node (ref "U2") (pin "15") (pinfunction "P0.02/AIN0_15") (pintype "bidirectional"))
    )
    (net (code "74") (name "unconnected-(U2-P0.23-Pad41)") (class "Default")
      (node (ref "U2") (pin "41") (pinfunction "P0.23_41") (pintype "bidirectional"))
    )
    (net (code "75") (name "unconnected-(U2-P0.24-Pad40)") (class "Default")
      (node (ref "U2") (pin "40") (pinfunction "P0.24_40") (pintype "bidirectional"))
    )
    (net (code "76") (name "unconnected-(U3-INT{slash}CLKOUT-Pad7)") (class "Default")
      (node (ref "U3") (pin "7") (pinfunction "INT/CLKOUT_7") (pintype "bidirectional"))
    )
  )
)
